# sample.net
KiCad netlist of a schematic drawn in EAGLE
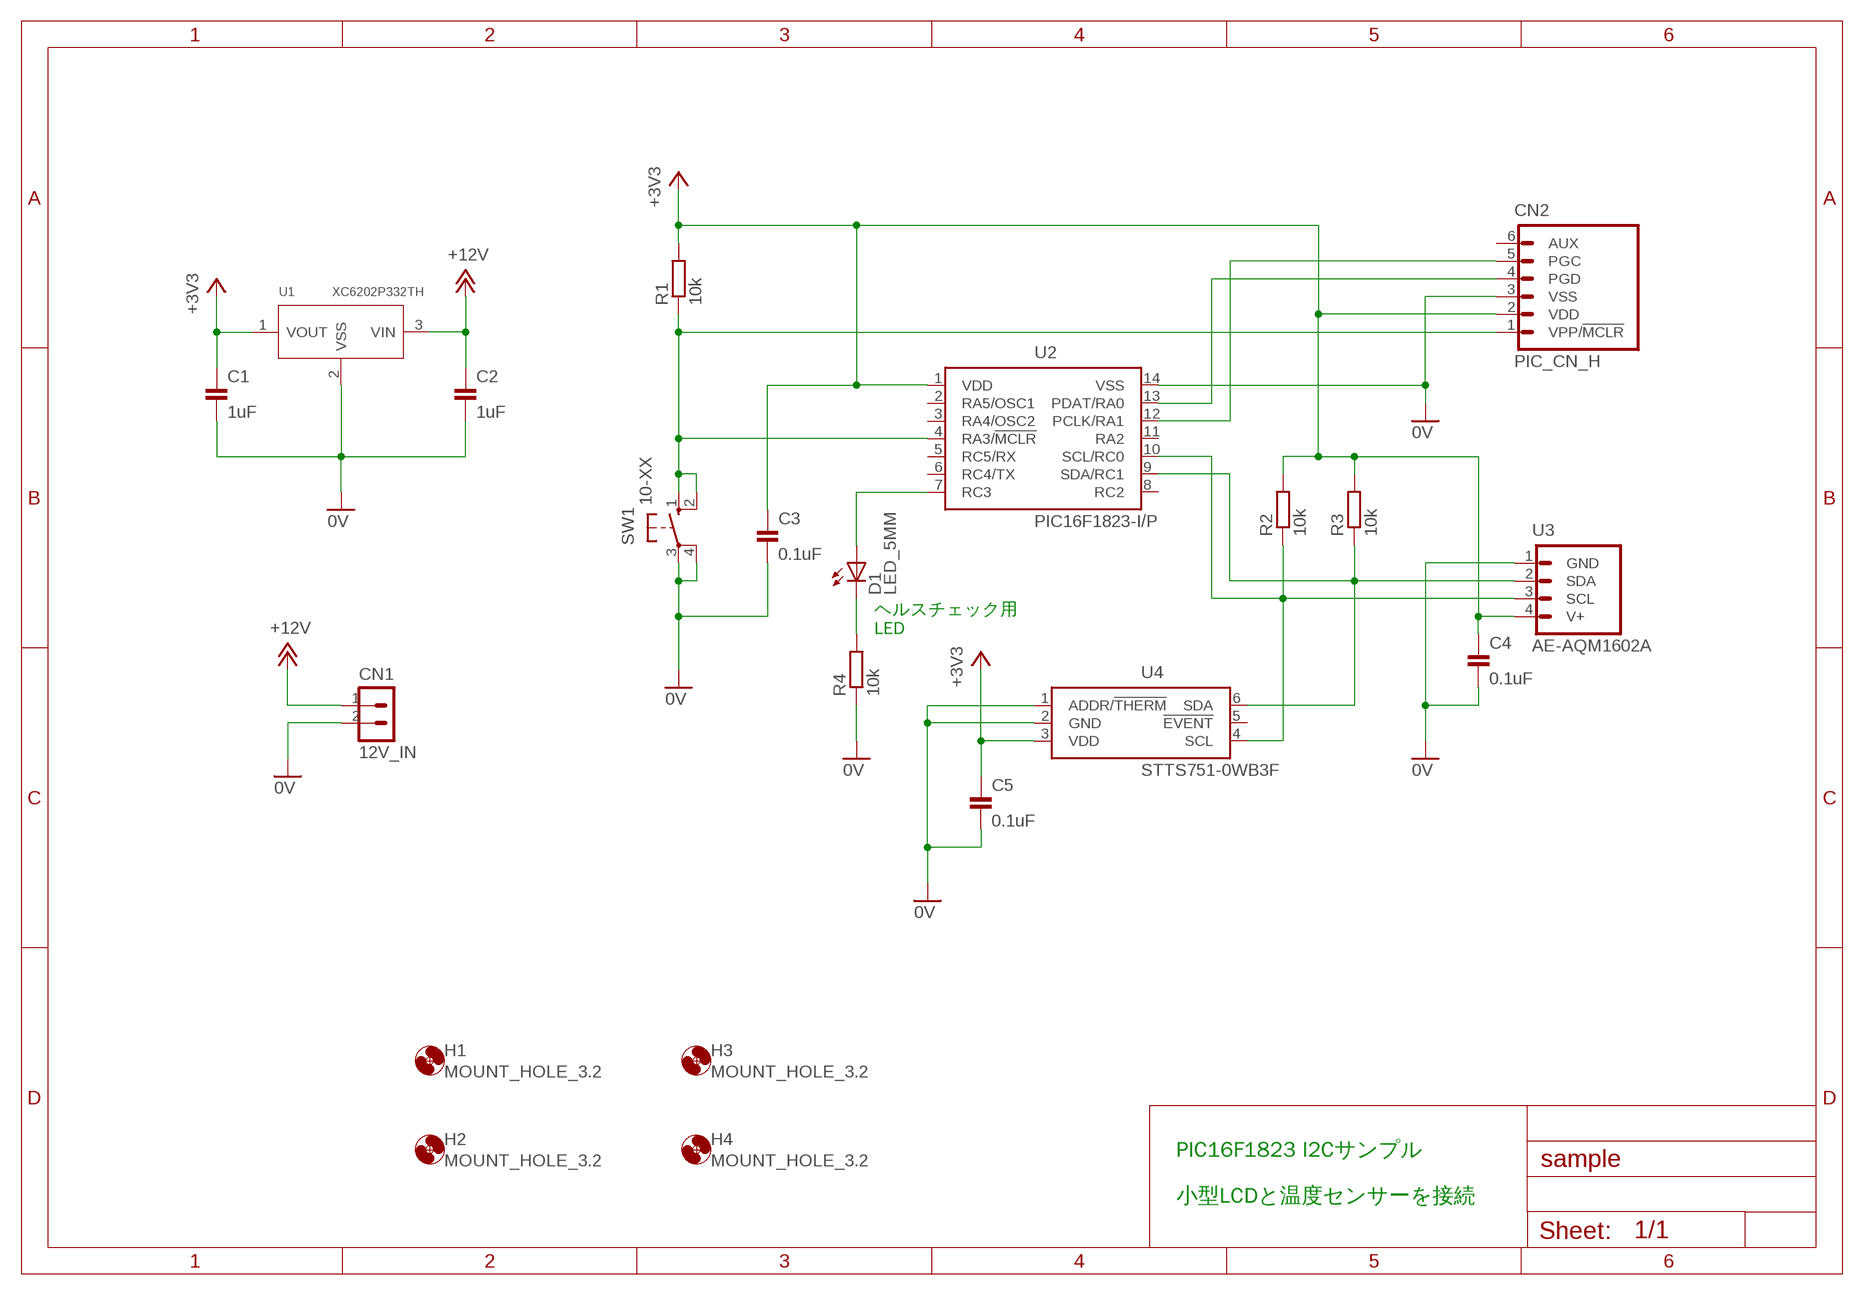
[diagram p0: schematic, sheet 1]

(export (version "E")
  (design (tool "Eeschema 10.0.6"))
  (components
    (comp (ref "C1")
      (value "1uF")
      (footprint "eagle-import:CAP_200MIL")
      (libsource (lib "eagle-import") (part "CAP_200MIL"))
    )
    (comp (ref "C2")
      (value "1uF")
      (footprint "eagle-import:CAP_200MIL")
      (libsource (lib "eagle-import") (part "CAP_200MIL"))
    )
    (comp (ref "C3")
      (value "0.1uF")
      (footprint "eagle-import:CAP_200MIL")
      (libsource (lib "eagle-import") (part "CAP_200MIL"))
    )
    (comp (ref "C4")
      (value "0.1uF")
      (footprint "eagle-import:CAP_200MIL")
      (libsource (lib "eagle-import") (part "CAP_200MIL"))
    )
    (comp (ref "C5")
      (value "0.1uF")
      (footprint "eagle-import:CAP_200MIL")
      (libsource (lib "eagle-import") (part "CAP_200MIL"))
    )
    (comp (ref "CN1")
      (value "12V_IN")
      (footprint "eagle-import:HEADER_L_2PIN")
      (libsource (lib "eagle-import") (part "CONN_2PIN-L"))
    )
    (comp (ref "CN2")
      (value "PIC_CN_H")
      (footprint "eagle-import:HEADER_6PIN")
      (libsource (lib "eagle-import") (part "PIC_CN_H"))
    )
    (comp (ref "D1")
      (value "LED_5MM")
      (footprint "eagle-import:LED5MM")
      (libsource (lib "eagle-import") (part "LED_5MM"))
    )
    (comp (ref "H1")
      (value "MOUNT_HOLE_3.2")
      (footprint "eagle-import:3,2")
      (libsource (lib "eagle-import") (part "MOUNT_HOLE_3.2"))
    )
    (comp (ref "H2")
      (value "MOUNT_HOLE_3.2")
      (footprint "eagle-import:3,2")
      (libsource (lib "eagle-import") (part "MOUNT_HOLE_3.2"))
    )
    (comp (ref "H3")
      (value "MOUNT_HOLE_3.2")
      (footprint "eagle-import:3,2")
      (libsource (lib "eagle-import") (part "MOUNT_HOLE_3.2"))
    )
    (comp (ref "H4")
      (value "MOUNT_HOLE_3.2")
      (footprint "eagle-import:3,2")
      (libsource (lib "eagle-import") (part "MOUNT_HOLE_3.2"))
    )
    (comp (ref "R1")
      (value "10k")
      (footprint "eagle-import:RESISTOR_0207_300MIL")
      (libsource (lib "eagle-import") (part "RESISTOR_300MIL"))
    )
    (comp (ref "R2")
      (value "10k")
      (footprint "eagle-import:RESISTOR_0207_300MIL")
      (libsource (lib "eagle-import") (part "RESISTOR_300MIL"))
    )
    (comp (ref "R3")
      (value "10k")
      (footprint "eagle-import:RESISTOR_0207_300MIL")
      (libsource (lib "eagle-import") (part "RESISTOR_300MIL"))
    )
    (comp (ref "R4")
      (value "10k")
      (footprint "eagle-import:RESISTOR_0207_300MIL")
      (libsource (lib "eagle-import") (part "RESISTOR_300MIL"))
    )
    (comp (ref "SW1")
      (value "10-XX")
      (footprint "eagle-import:B3F-10XX")
      (libsource (lib "eagle-import") (part "10-XX"))
    )
    (comp (ref "U1")
      (value "XC6202P332TH")
      (footprint "eagle-import:TO92-LINE")
      (libsource (lib "eagle-import") (part "XC6202P332TH"))
    )
    (comp (ref "U2")
      (value "PIC16F1823-I/P")
      (footprint "eagle-import:DIL14")
      (libsource (lib "eagle-import") (part "PIC16F1823-I/P"))
    )
    (comp (ref "U3")
      (value "AE-AQM1602A")
      (footprint "eagle-import:AE-AQM1602A")
      (libsource (lib "eagle-import") (part "AE-AQM1602A"))
    )
    (comp (ref "U4")
      (value "STTS751-0WB3F")
      (footprint "eagle-import:SOT23-6L")
      (libsource (lib "eagle-import") (part "STTS751-0WB3F"))
    )
  )
  (nets
    (net (code "1") (name "+3V3") (class "Default")
      (node (ref "C1") (pin "1") (pinfunction "1_1") (pintype "passive"))
      (node (ref "C3") (pin "1") (pinfunction "1_1") (pintype "passive"))
      (node (ref "C4") (pin "1") (pinfunction "1_1") (pintype "passive"))
      (node (ref "C5") (pin "1") (pinfunction "1_1") (pintype "passive"))
      (node (ref "CN2") (pin "2") (pinfunction "VDD_2") (pintype "passive"))
      (node (ref "R1") (pin "2") (pinfunction "2_2") (pintype "passive"))
      (node (ref "R2") (pin "2") (pinfunction "2_2") (pintype "passive"))
      (node (ref "R3") (pin "2") (pinfunction "2_2") (pintype "passive"))
      (node (ref "U1") (pin "1") (pinfunction "VOUT_1") (pintype "passive"))
      (node (ref "U2") (pin "1") (pinfunction "VDD_1") (pintype "passive"))
      (node (ref "U3") (pin "4") (pinfunction "V+_4") (pintype "passive"))
      (node (ref "U4") (pin "3") (pinfunction "VDD_3") (pintype "passive"))
    )
    (net (code "2") (name "+12V") (class "Default")
      (node (ref "C2") (pin "1") (pinfunction "1_1") (pintype "passive"))
      (node (ref "CN1") (pin "1") (pinfunction "1_1") (pintype "passive"))
      (node (ref "U1") (pin "3") (pinfunction "VIN_3") (pintype "passive"))
    )
    (net (code "3") (name "0V") (class "Default")
      (node (ref "C1") (pin "2") (pinfunction "2_2") (pintype "passive"))
      (node (ref "C2") (pin "2") (pinfunction "2_2") (pintype "passive"))
      (node (ref "C3") (pin "2") (pinfunction "2_2") (pintype "passive"))
      (node (ref "C4") (pin "2") (pinfunction "2_2") (pintype "passive"))
      (node (ref "C5") (pin "2") (pinfunction "2_2") (pintype "passive"))
      (node (ref "CN1") (pin "2") (pinfunction "2_2") (pintype "passive"))
      (node (ref "CN2") (pin "3") (pinfunction "VSS_3") (pintype "passive"))
      (node (ref "R4") (pin "1") (pinfunction "1_1") (pintype "passive"))
      (node (ref "SW1") (pin "3") (pinfunction "P_3") (pintype "passive"))
      (node (ref "SW1") (pin "4") (pinfunction "P1_4") (pintype "passive"))
      (node (ref "U1") (pin "2") (pinfunction "VSS_2") (pintype "passive"))
      (node (ref "U2") (pin "14") (pinfunction "VSS_14") (pintype "passive"))
      (node (ref "U3") (pin "1") (pinfunction "GND_1") (pintype "passive"))
      (node (ref "U4") (pin "1") (pinfunction "ADDR/~{THERM}_1") (pintype "bidirectional"))
      (node (ref "U4") (pin "2") (pinfunction "GND_2") (pintype "passive"))
    )
    (net (code "4") (name "Net-(CN2-PGC)") (class "Default")
      (node (ref "CN2") (pin "5") (pinfunction "PGC_5") (pintype "input"))
      (node (ref "U2") (pin "12") (pinfunction "PCLK/RA1_12") (pintype "bidirectional"))
    )
    (net (code "5") (name "Net-(CN2-PGD)") (class "Default")
      (node (ref "CN2") (pin "4") (pinfunction "PGD_4") (pintype "bidirectional"))
      (node (ref "U2") (pin "13") (pinfunction "PDAT/RA0_13") (pintype "bidirectional"))
    )
    (net (code "6") (name "Net-(CN2-VPP{slash}~{MCLR})") (class "Default")
      (node (ref "CN2") (pin "1") (pinfunction "VPP/~{MCLR}_1") (pintype "input"))
      (node (ref "R1") (pin "1") (pinfunction "1_1") (pintype "passive"))
      (node (ref "SW1") (pin "1") (pinfunction "S_1") (pintype "passive"))
      (node (ref "SW1") (pin "2") (pinfunction "S1_2") (pintype "passive"))
      (node (ref "U2") (pin "4") (pinfunction "RA3/~{MCLR}_4") (pintype "bidirectional"))
    )
    (net (code "7") (name "Net-(D1-C)") (class "Default")
      (node (ref "D1") (pin "K") (pinfunction "C_K") (pintype "passive"))
      (node (ref "R4") (pin "2") (pinfunction "2_2") (pintype "passive"))
    )
    (net (code "8") (name "Net-(U2-RC3)") (class "Default")
      (node (ref "D1") (pin "A") (pinfunction "A_A") (pintype "passive"))
      (node (ref "U2") (pin "7") (pinfunction "RC3_7") (pintype "bidirectional"))
    )
    (net (code "9") (name "Net-(U2-SCL{slash}RC0)") (class "Default")
      (node (ref "R2") (pin "1") (pinfunction "1_1") (pintype "passive"))
      (node (ref "U2") (pin "10") (pinfunction "SCL/RC0_10") (pintype "bidirectional"))
      (node (ref "U3") (pin "3") (pinfunction "SCL_3") (pintype "bidirectional"))
      (node (ref "U4") (pin "4") (pinfunction "SCL_4") (pintype "bidirectional"))
    )
    (net (code "10") (name "Net-(U2-SDA{slash}RC1)") (class "Default")
      (node (ref "R3") (pin "1") (pinfunction "1_1") (pintype "passive"))
      (node (ref "U2") (pin "9") (pinfunction "SDA/RC1_9") (pintype "bidirectional"))
      (node (ref "U3") (pin "2") (pinfunction "SDA_2") (pintype "bidirectional"))
      (node (ref "U4") (pin "6") (pinfunction "SDA_6") (pintype "bidirectional"))
    )
    (net (code "11") (name "unconnected-(CN2-AUX-Pad6)") (class "Default")
      (node (ref "CN2") (pin "6") (pinfunction "AUX_6") (pintype "bidirectional"))
    )
    (net (code "12") (name "unconnected-(U2-RA2-Pad11)") (class "Default")
      (node (ref "U2") (pin "11") (pinfunction "RA2_11") (pintype "bidirectional"))
    )
    (net (code "13") (name "unconnected-(U2-RA4{slash}OSC2-Pad3)") (class "Default")
      (node (ref "U2") (pin "3") (pinfunction "RA4/OSC2_3") (pintype "bidirectional"))
    )
    (net (code "14") (name "unconnected-(U2-RA5{slash}OSC1-Pad2)") (class "Default")
      (node (ref "U2") (pin "2") (pinfunction "RA5/OSC1_2") (pintype "bidirectional"))
    )
    (net (code "15") (name "unconnected-(U2-RC2-Pad8)") (class "Default")
      (node (ref "U2") (pin "8") (pinfunction "RC2_8") (pintype "bidirectional"))
    )
    (net (code "16") (name "unconnected-(U2-RC4{slash}TX-Pad6)") (class "Default")
      (node (ref "U2") (pin "6") (pinfunction "RC4/TX_6") (pintype "bidirectional"))
    )
    (net (code "17") (name "unconnected-(U2-RC5{slash}RX-Pad5)") (class "Default")
      (node (ref "U2") (pin "5") (pinfunction "RC5/RX_5") (pintype "bidirectional"))
    )
    (net (code "18") (name "unconnected-(U4-~{EVENT}-Pad5)") (class "Default")
      (node (ref "U4") (pin "5") (pinfunction "~{EVENT}_5") (pintype "bidirectional"))
    )
  )
)
